# esquema.net
KiCad netlist of a schematic drawn in EAGLE
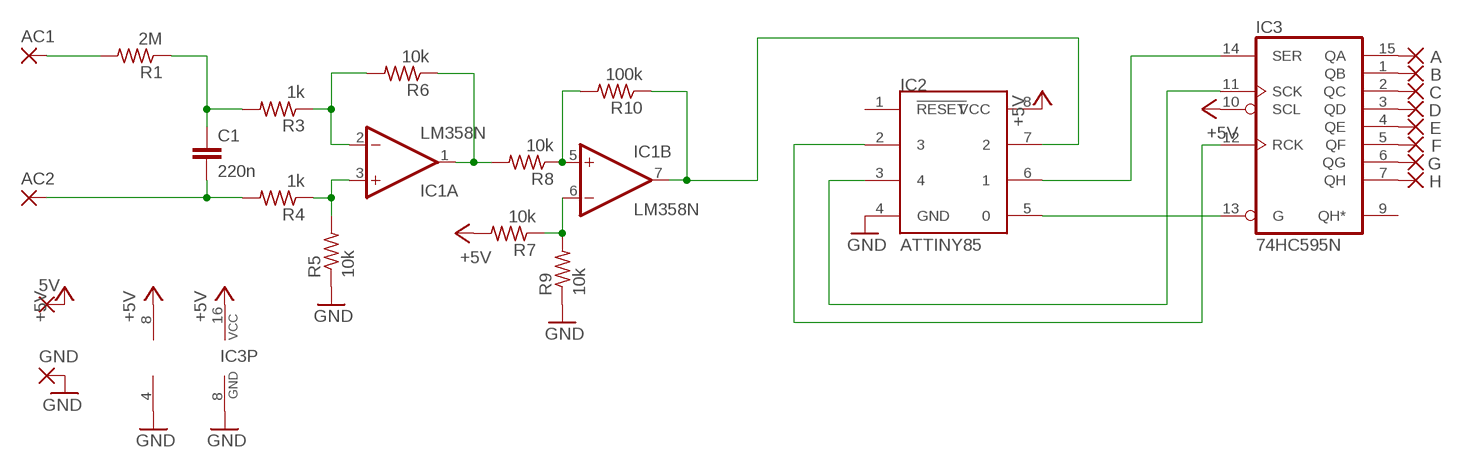
[diagram p0: schematic, sheet 1]

(export (version "E")
  (design (tool "Eeschema 10.0.6"))
  (components
    (comp (ref "5V")
      (value "2,15/1,0")
      (footprint "eagle-import:2,15_1,0")
      (libsource (lib "eagle-import") (part "2,15/1,0"))
    )
    (comp (ref "A")
      (value "2,15/1,0")
      (footprint "eagle-import:2,15_1,0")
      (libsource (lib "eagle-import") (part "2,15/1,0"))
    )
    (comp (ref "AC1")
      (value "2,15/1,0")
      (footprint "eagle-import:2,15_1,0")
      (libsource (lib "eagle-import") (part "2,15/1,0"))
    )
    (comp (ref "AC2")
      (value "2,15/1,0")
      (footprint "eagle-import:2,15_1,0")
      (libsource (lib "eagle-import") (part "2,15/1,0"))
    )
    (comp (ref "B")
      (value "2,15/1,0")
      (footprint "eagle-import:2,15_1,0")
      (libsource (lib "eagle-import") (part "2,15/1,0"))
    )
    (comp (ref "C")
      (value "2,15/1,0")
      (footprint "eagle-import:2,15_1,0")
      (libsource (lib "eagle-import") (part "2,15/1,0"))
    )
    (comp (ref "C1")
      (value "220n")
      (footprint "eagle-import:C075-052X106")
      (libsource (lib "eagle-import") (part "C-EU075-052X106"))
    )
    (comp (ref "D")
      (value "2,15/1,0")
      (footprint "eagle-import:2,15_1,0")
      (libsource (lib "eagle-import") (part "2,15/1,0"))
    )
    (comp (ref "E")
      (value "2,15/1,0")
      (footprint "eagle-import:2,15_1,0")
      (libsource (lib "eagle-import") (part "2,15/1,0"))
    )
    (comp (ref "F")
      (value "2,15/1,0")
      (footprint "eagle-import:2,15_1,0")
      (libsource (lib "eagle-import") (part "2,15/1,0"))
    )
    (comp (ref "G")
      (value "2,15/1,0")
      (footprint "eagle-import:2,15_1,0")
      (libsource (lib "eagle-import") (part "2,15/1,0"))
    )
    (comp (ref "GND")
      (value "2,15/1,0")
      (footprint "eagle-import:2,15_1,0")
      (libsource (lib "eagle-import") (part "2,15/1,0"))
    )
    (comp (ref "H")
      (value "2,15/1,0")
      (footprint "eagle-import:2,15_1,0")
      (libsource (lib "eagle-import") (part "2,15/1,0"))
    )
    (comp (ref "IC1")
      (value "LM358N")
      (footprint "eagle-import:DIL08")
      (libsource (lib "eagle-import") (part "LM358N"))
    )
    (comp (ref "IC2")
      (value "ATTINY85")
      (footprint "eagle-import:8P3")
      (libsource (lib "eagle-import") (part "ATTINY85"))
    )
    (comp (ref "IC3")
      (value "74HC595N")
      (footprint "eagle-import:DIL16")
      (libsource (lib "eagle-import") (part "74595NHC"))
    )
    (comp (ref "R1")
      (value "2M")
      (footprint "eagle-import:0207_10")
      (libsource (lib "eagle-import") (part "R-US_0207/10"))
    )
    (comp (ref "R3")
      (value "1k")
      (footprint "eagle-import:0207_10")
      (libsource (lib "eagle-import") (part "R-US_0207/10"))
    )
    (comp (ref "R4")
      (value "1k")
      (footprint "eagle-import:0207_10")
      (libsource (lib "eagle-import") (part "R-US_0207/10"))
    )
    (comp (ref "R5")
      (value "10k")
      (footprint "eagle-import:0207_10")
      (libsource (lib "eagle-import") (part "R-US_0207/10"))
    )
    (comp (ref "R6")
      (value "10k")
      (footprint "eagle-import:0207_10")
      (libsource (lib "eagle-import") (part "R-US_0207/10"))
    )
    (comp (ref "R7")
      (value "10k")
      (footprint "eagle-import:0207_10")
      (libsource (lib "eagle-import") (part "R-US_0207/10"))
    )
    (comp (ref "R8")
      (value "10k")
      (footprint "eagle-import:0207_10")
      (libsource (lib "eagle-import") (part "R-US_0207/10"))
    )
    (comp (ref "R9")
      (value "10k")
      (footprint "eagle-import:0207_10")
      (libsource (lib "eagle-import") (part "R-US_0207/10"))
    )
    (comp (ref "R10")
      (value "100k")
      (footprint "eagle-import:0207_10")
      (libsource (lib "eagle-import") (part "R-US_0207/10"))
    )
  )
  (nets
    (net (code "1") (name "+5V") (class "Default")
      (node (ref "5V") (pin "1") (pinfunction "P_1") (pintype "passive"))
      (node (ref "IC1") (pin "8") (pinfunction "V+_8") (pintype "power_in"))
      (node (ref "IC2") (pin "8") (pinfunction "VCC_8") (pintype "power_in"))
      (node (ref "IC3") (pin "10") (pinfunction "SCL_10") (pintype "input"))
      (node (ref "IC3") (pin "16") (pinfunction "VCC_16") (pintype "power_in"))
      (node (ref "R7") (pin "2") (pinfunction "2_2") (pintype "passive"))
    )
    (net (code "2") (name "GND") (class "Default")
      (node (ref "GND") (pin "1") (pinfunction "P_1") (pintype "passive"))
      (node (ref "IC1") (pin "4") (pinfunction "V-_4") (pintype "power_in"))
      (node (ref "IC2") (pin "4") (pinfunction "GND_4") (pintype "power_in"))
      (node (ref "IC3") (pin "8") (pinfunction "GND_8") (pintype "power_in"))
      (node (ref "R5") (pin "1") (pinfunction "1_1") (pintype "passive"))
      (node (ref "R9") (pin "1") (pinfunction "1_1") (pintype "passive"))
    )
    (net (code "3") (name "Net-(A-P)") (class "Default")
      (node (ref "A") (pin "1") (pinfunction "P_1") (pintype "passive"))
      (node (ref "IC3") (pin "15") (pinfunction "QA_15") (pintype "tri_state"))
    )
    (net (code "4") (name "Net-(AC1-P)") (class "Default")
      (node (ref "AC1") (pin "1") (pinfunction "P_1") (pintype "passive"))
      (node (ref "R1") (pin "2") (pinfunction "2_2") (pintype "passive"))
    )
    (net (code "5") (name "Net-(AC2-P)") (class "Default")
      (node (ref "AC2") (pin "1") (pinfunction "P_1") (pintype "passive"))
      (node (ref "C1") (pin "2") (pinfunction "2_2") (pintype "passive"))
      (node (ref "R4") (pin "2") (pinfunction "2_2") (pintype "passive"))
    )
    (net (code "6") (name "Net-(B-P)") (class "Default")
      (node (ref "B") (pin "1") (pinfunction "P_1") (pintype "passive"))
      (node (ref "IC3") (pin "1") (pinfunction "QB_1") (pintype "tri_state"))
    )
    (net (code "7") (name "Net-(C-P)") (class "Default")
      (node (ref "C") (pin "1") (pinfunction "P_1") (pintype "passive"))
      (node (ref "IC3") (pin "2") (pinfunction "QC_2") (pintype "tri_state"))
    )
    (net (code "8") (name "Net-(C1-Pad1)") (class "Default")
      (node (ref "C1") (pin "1") (pinfunction "1_1") (pintype "passive"))
      (node (ref "R1") (pin "1") (pinfunction "1_1") (pintype "passive"))
      (node (ref "R3") (pin "2") (pinfunction "2_2") (pintype "passive"))
    )
    (net (code "9") (name "Net-(D-P)") (class "Default")
      (node (ref "D") (pin "1") (pinfunction "P_1") (pintype "passive"))
      (node (ref "IC3") (pin "3") (pinfunction "QD_3") (pintype "tri_state"))
    )
    (net (code "10") (name "Net-(E-P)") (class "Default")
      (node (ref "E") (pin "1") (pinfunction "P_1") (pintype "passive"))
      (node (ref "IC3") (pin "4") (pinfunction "QE_4") (pintype "tri_state"))
    )
    (net (code "11") (name "Net-(F-P)") (class "Default")
      (node (ref "F") (pin "1") (pinfunction "P_1") (pintype "passive"))
      (node (ref "IC3") (pin "5") (pinfunction "QF_5") (pintype "tri_state"))
    )
    (net (code "12") (name "Net-(G-P)") (class "Default")
      (node (ref "G") (pin "1") (pinfunction "P_1") (pintype "passive"))
      (node (ref "IC3") (pin "6") (pinfunction "QG_6") (pintype "tri_state"))
    )
    (net (code "13") (name "Net-(H-P)") (class "Default")
      (node (ref "H") (pin "1") (pinfunction "P_1") (pintype "passive"))
      (node (ref "IC3") (pin "7") (pinfunction "QH_7") (pintype "tri_state"))
    )
    (net (code "14") (name "Net-(IC1A-+IN)") (class "Default")
      (node (ref "IC1") (pin "3") (pinfunction "+IN_3") (pintype "input"))
      (node (ref "R4") (pin "1") (pinfunction "1_1") (pintype "passive"))
      (node (ref "R5") (pin "2") (pinfunction "2_2") (pintype "passive"))
    )
    (net (code "15") (name "Net-(IC1A--IN)") (class "Default")
      (node (ref "IC1") (pin "2") (pinfunction "-IN_2") (pintype "input"))
      (node (ref "R3") (pin "1") (pinfunction "1_1") (pintype "passive"))
      (node (ref "R6") (pin "2") (pinfunction "2_2") (pintype "passive"))
    )
    (net (code "16") (name "Net-(IC1A-OUT)") (class "Default")
      (node (ref "IC1") (pin "1") (pinfunction "OUT_1") (pintype "output"))
      (node (ref "R6") (pin "1") (pinfunction "1_1") (pintype "passive"))
      (node (ref "R8") (pin "2") (pinfunction "2_2") (pintype "passive"))
    )
    (net (code "17") (name "Net-(IC1B-+IN)") (class "Default")
      (node (ref "IC1") (pin "5") (pinfunction "+IN_5") (pintype "input"))
      (node (ref "R10") (pin "2") (pinfunction "2_2") (pintype "passive"))
      (node (ref "R8") (pin "1") (pinfunction "1_1") (pintype "passive"))
    )
    (net (code "18") (name "Net-(IC1B--IN)") (class "Default")
      (node (ref "IC1") (pin "6") (pinfunction "-IN_6") (pintype "input"))
      (node (ref "R7") (pin "1") (pinfunction "1_1") (pintype "passive"))
      (node (ref "R9") (pin "2") (pinfunction "2_2") (pintype "passive"))
    )
    (net (code "19") (name "Net-(IC1B-OUT)") (class "Default")
      (node (ref "IC1") (pin "7") (pinfunction "OUT_7") (pintype "output"))
      (node (ref "IC2") (pin "7") (pinfunction "2_7") (pintype "bidirectional"))
      (node (ref "R10") (pin "1") (pinfunction "1_1") (pintype "passive"))
    )
    (net (code "20") (name "Net-(IC2-0)") (class "Default")
      (node (ref "IC2") (pin "5") (pinfunction "0_5") (pintype "bidirectional"))
      (node (ref "IC3") (pin "13") (pinfunction "G_13") (pintype "input"))
    )
    (net (code "21") (name "Net-(IC2-1)") (class "Default")
      (node (ref "IC2") (pin "6") (pinfunction "1_6") (pintype "bidirectional"))
      (node (ref "IC3") (pin "14") (pinfunction "SER_14") (pintype "input"))
    )
    (net (code "22") (name "Net-(IC2-3)") (class "Default")
      (node (ref "IC2") (pin "2") (pinfunction "3_2") (pintype "bidirectional"))
      (node (ref "IC3") (pin "12") (pinfunction "RCK_12") (pintype "input"))
    )
    (net (code "23") (name "Net-(IC2-4)") (class "Default")
      (node (ref "IC2") (pin "3") (pinfunction "4_3") (pintype "bidirectional"))
      (node (ref "IC3") (pin "11") (pinfunction "SCK_11") (pintype "input"))
    )
    (net (code "24") (name "unconnected-(IC2-~{RESET}-Pad1)") (class "Default")
      (node (ref "IC2") (pin "1") (pinfunction "~{RESET}_1") (pintype "bidirectional"))
    )
    (net (code "25") (name "unconnected-(IC3A-QH*-Pad9)") (class "Default")
      (node (ref "IC3") (pin "9") (pinfunction "QH*_9") (pintype "tri_state"))
    )
  )
)
